# RH100.net
KiCad netlist of a schematic drawn in Altium Designer
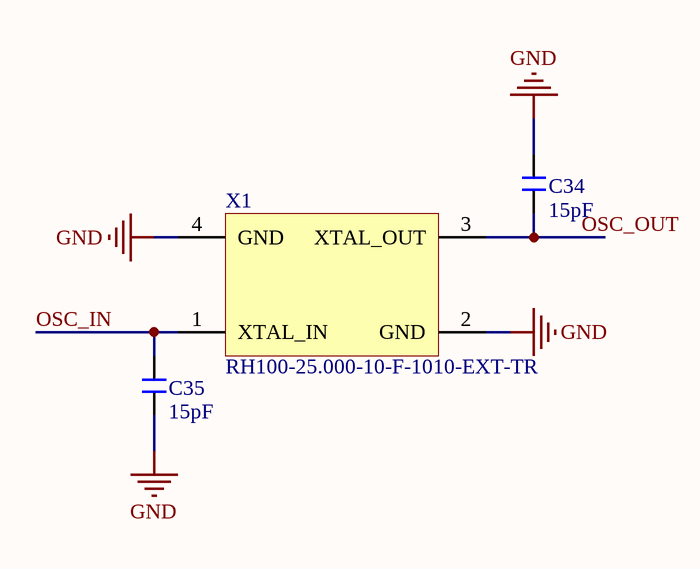
[diagram p0: RH100.SchDoc]

(export (version "E")
  (design (tool "Eeschema 10.0.6"))
  (components
    (comp (ref "C34")
      (value "15pF")
      (footprint "402 capacitor - duplicate")
      (description "CAP SMD 402")
      (fields (field (name "MPN") "GRM1555C1H150JA01D") (field (name "Comment") "0402 capacitor"))
      (libsource (lib "Schlib1") (part "CAP SMD 402"))
    )
    (comp (ref "C35")
      (value "15pF")
      (footprint "402 capacitor - duplicate")
      (description "CAP SMD 402")
      (fields (field (name "MPN") "GRM1555C1H150JA01D") (field (name "Comment") "0402 capacitor"))
      (libsource (lib "Schlib1") (part "CAP SMD 402"))
    )
    (comp (ref "X1")
      (value "RH100-25.000-10-F-1010-EXT-TR")
      (footprint "RH100-25.000-10-F-1010-EXT-TR")
      (description "CRYSTAL 25.0000MHZ 10PF SMD")
      (libsource (lib "Schlib1") (part "RH100-25.000-10-F-1010-EXT-TR"))
    )
  )
  (nets
    (net (code "1") (name "/OSC_IN") (class "Default")
      (node (ref "C35") (pin "2") (pintype "passive"))
      (node (ref "X1") (pin "1") (pinfunction "XTAL_IN_1") (pintype "passive"))
    )
    (net (code "2") (name "/OSC_OUT") (class "Default")
      (node (ref "C34") (pin "2") (pintype "passive"))
      (node (ref "X1") (pin "3") (pinfunction "XTAL_OUT_3") (pintype "passive"))
    )
    (net (code "3") (name "GND") (class "Default")
      (node (ref "C34") (pin "1") (pintype "passive"))
      (node (ref "C35") (pin "1") (pintype "passive"))
      (node (ref "X1") (pin "2") (pinfunction "GND_2") (pintype "passive"))
      (node (ref "X1") (pin "4") (pinfunction "GND_4") (pintype "passive"))
    )
  )
)
